# schematic.net
KiCad netlist of a schematic drawn in EAGLE
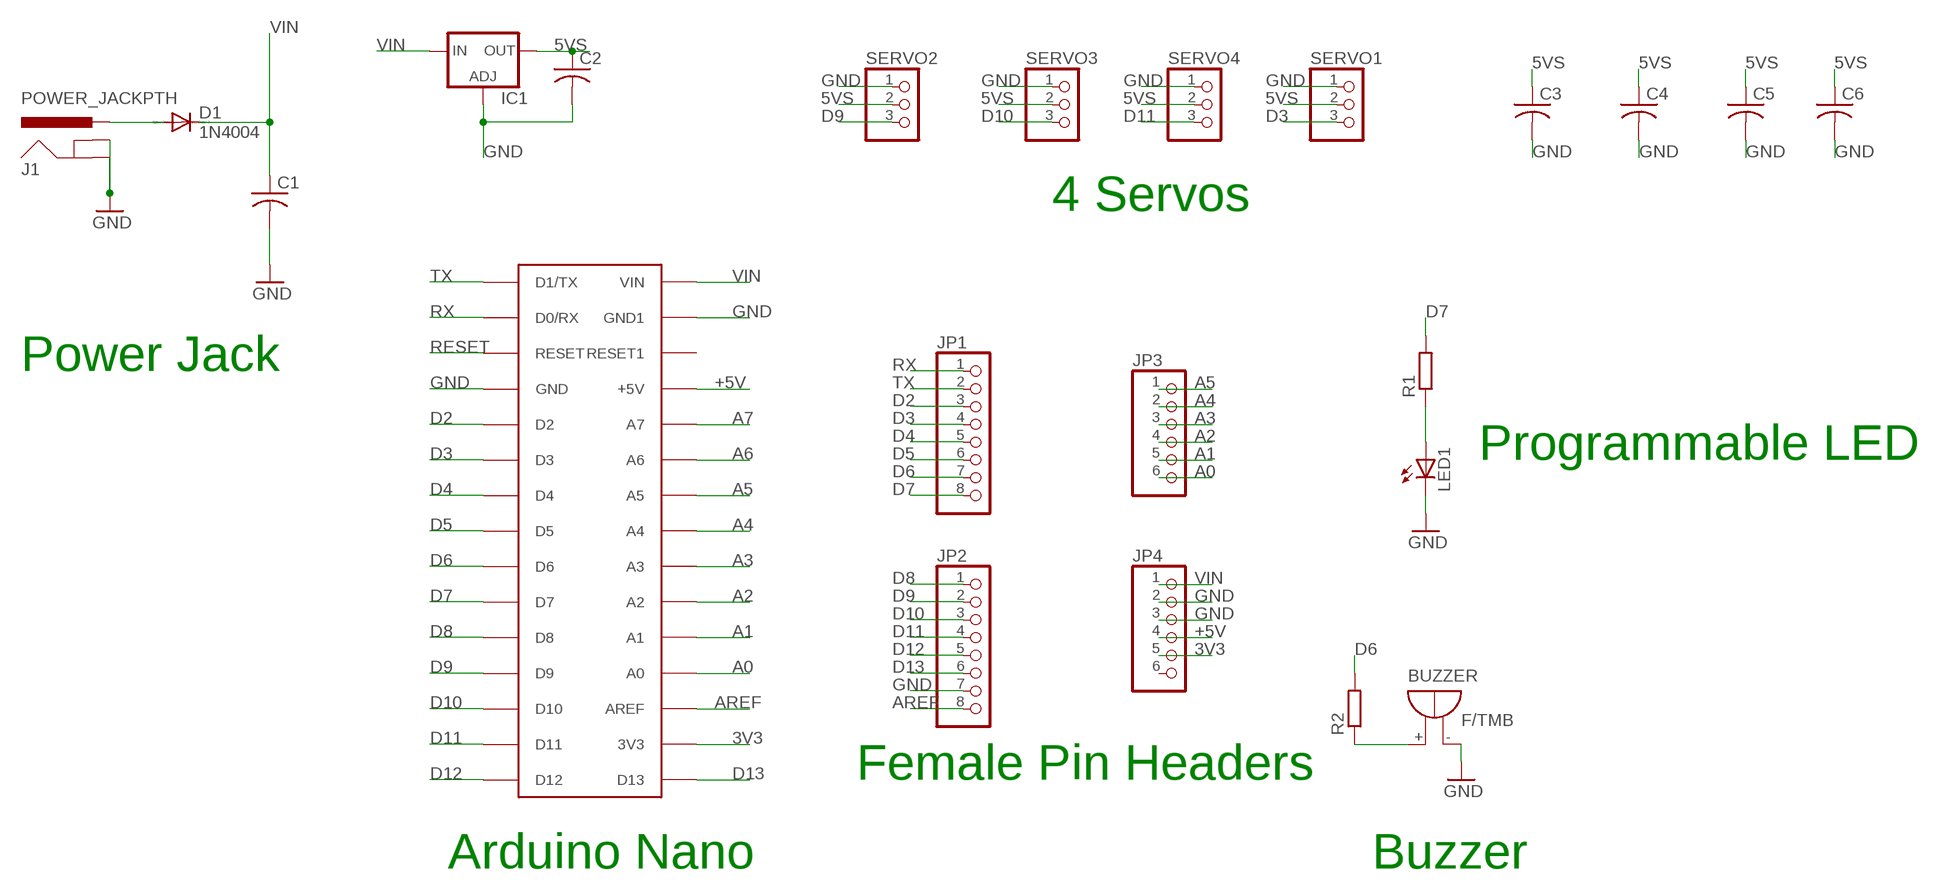
[diagram p0: schematic, sheet 1]

(export (version "E")
  (design (tool "Eeschema 10.0.6"))
  (components
    (comp (ref "BUZZER")
      (value "F/TMB")
      (footprint "eagle-import:F_TMB")
      (libsource (lib "eagle-import") (part "F/TMB"))
    )
    (comp (ref "C1")
      (value "C-USC1206")
      (footprint "eagle-import:C1206")
      (libsource (lib "eagle-import") (part "C-USC1206"))
    )
    (comp (ref "C2")
      (value "C-USC1206")
      (footprint "eagle-import:C1206")
      (libsource (lib "eagle-import") (part "C-USC1206"))
    )
    (comp (ref "C3")
      (value "C-USC0805")
      (footprint "eagle-import:C0805")
      (libsource (lib "eagle-import") (part "C-USC0805"))
    )
    (comp (ref "C4")
      (value "C-USC0805")
      (footprint "eagle-import:C0805")
      (libsource (lib "eagle-import") (part "C-USC0805"))
    )
    (comp (ref "C5")
      (value "C-USC0805")
      (footprint "eagle-import:C0805")
      (libsource (lib "eagle-import") (part "C-USC0805"))
    )
    (comp (ref "C6")
      (value "C-USC0805")
      (footprint "eagle-import:C0805")
      (libsource (lib "eagle-import") (part "C-USC0805"))
    )
    (comp (ref "D1")
      (value "1N4004")
      (footprint "eagle-import:DO41-10")
      (libsource (lib "eagle-import") (part "1N4004"))
    )
    (comp (ref "IC1")
      (value "LD117AS33TR")
      (footprint "eagle-import:SOT223")
      (libsource (lib "eagle-import") (part "LD117A?S33TR"))
    )
    (comp (ref "J1")
      (value "POWER_JACKPTH")
      (footprint "eagle-import:POWER_JACK_PTH")
      (libsource (lib "eagle-import") (part "POWER_JACKPTH"))
    )
    (comp (ref "JP1")
      (value "PINHD-1X8")
      (footprint "eagle-import:1X08")
      (libsource (lib "eagle-import") (part "PINHD-1X8"))
    )
    (comp (ref "JP2")
      (value "PINHD-1X8")
      (footprint "eagle-import:1X08")
      (libsource (lib "eagle-import") (part "PINHD-1X8"))
    )
    (comp (ref "JP3")
      (value "PINHD-1X6")
      (footprint "eagle-import:1X06")
      (libsource (lib "eagle-import") (part "PINHD-1X6"))
    )
    (comp (ref "JP4")
      (value "PINHD-1X6")
      (footprint "eagle-import:1X06")
      (libsource (lib "eagle-import") (part "PINHD-1X6"))
    )
    (comp (ref "LED1")
      (value "LED5MM")
      (footprint "eagle-import:LED5MM")
      (libsource (lib "eagle-import") (part "LED5MM"))
    )
    (comp (ref "R1")
      (value "R-EU_0207/10")
      (footprint "eagle-import:0207_10")
      (libsource (lib "eagle-import") (part "R-EU_0207/10"))
    )
    (comp (ref "R2")
      (value "R-EU_0207/10")
      (footprint "eagle-import:0207_10")
      (libsource (lib "eagle-import") (part "R-EU_0207/10"))
    )
    (comp (ref "SERVO1")
      (value "PINHD-1X3")
      (footprint "eagle-import:1X03")
      (libsource (lib "eagle-import") (part "PINHD-1X3"))
    )
    (comp (ref "SERVO2")
      (value "PINHD-1X3")
      (footprint "eagle-import:1X03")
      (libsource (lib "eagle-import") (part "PINHD-1X3"))
    )
    (comp (ref "SERVO3")
      (value "PINHD-1X3")
      (footprint "eagle-import:1X03")
      (libsource (lib "eagle-import") (part "PINHD-1X3"))
    )
    (comp (ref "SERVO4")
      (value "PINHD-1X3")
      (footprint "eagle-import:1X03")
      (libsource (lib "eagle-import") (part "PINHD-1X3"))
    )
    (comp (ref "U$1")
      (value "ARDUINONANO")
      (footprint "eagle-import:PDIP-32")
      (libsource (lib "eagle-import") (part "ARDUINONANO"))
    )
  )
  (nets
    (net (code "1") (name "/+5V") (class "Default")
      (node (ref "JP4") (pin "4") (pinfunction "4_4") (pintype "passive"))
      (node (ref "U$1") (pin "+5V") (pinfunction "+5V_+5V") (pintype "bidirectional"))
    )
    (net (code "2") (name "/3V3") (class "Default")
      (node (ref "JP4") (pin "5") (pinfunction "5_5") (pintype "passive"))
      (node (ref "U$1") (pin "3V3") (pinfunction "3V3_3V3") (pintype "bidirectional"))
    )
    (net (code "3") (name "/5VS") (class "Default")
      (node (ref "C2") (pin "1") (pinfunction "1_1") (pintype "passive"))
      (node (ref "C3") (pin "1") (pinfunction "1_1") (pintype "passive"))
      (node (ref "C4") (pin "1") (pinfunction "1_1") (pintype "passive"))
      (node (ref "C5") (pin "1") (pinfunction "1_1") (pintype "passive"))
      (node (ref "C6") (pin "1") (pinfunction "1_1") (pintype "passive"))
      (node (ref "IC1") (pin "4") (pinfunction "OUT_4") (pintype "passive"))
      (node (ref "SERVO1") (pin "2") (pinfunction "2_2") (pintype "passive"))
      (node (ref "SERVO2") (pin "2") (pinfunction "2_2") (pintype "passive"))
      (node (ref "SERVO3") (pin "2") (pinfunction "2_2") (pintype "passive"))
      (node (ref "SERVO4") (pin "2") (pinfunction "2_2") (pintype "passive"))
    )
    (net (code "4") (name "/A0") (class "Default")
      (node (ref "JP3") (pin "6") (pinfunction "6_6") (pintype "passive"))
      (node (ref "U$1") (pin "A7") (pinfunction "A0_A7") (pintype "bidirectional"))
    )
    (net (code "5") (name "/A1") (class "Default")
      (node (ref "JP3") (pin "5") (pinfunction "5_5") (pintype "passive"))
      (node (ref "U$1") (pin "A6") (pinfunction "A1_A6") (pintype "bidirectional"))
    )
    (net (code "6") (name "/A2") (class "Default")
      (node (ref "JP3") (pin "4") (pinfunction "4_4") (pintype "passive"))
      (node (ref "U$1") (pin "A5") (pinfunction "A2_A5") (pintype "bidirectional"))
    )
    (net (code "7") (name "/A3") (class "Default")
      (node (ref "JP3") (pin "3") (pinfunction "3_3") (pintype "passive"))
      (node (ref "U$1") (pin "A4") (pinfunction "A3_A4") (pintype "bidirectional"))
    )
    (net (code "8") (name "/A4") (class "Default")
      (node (ref "JP3") (pin "2") (pinfunction "2_2") (pintype "passive"))
      (node (ref "U$1") (pin "A3") (pinfunction "A4_A3") (pintype "bidirectional"))
    )
    (net (code "9") (name "/A5") (class "Default")
      (node (ref "JP3") (pin "1") (pinfunction "1_1") (pintype "passive"))
      (node (ref "U$1") (pin "A2") (pinfunction "A5_A2") (pintype "bidirectional"))
    )
    (net (code "10") (name "/A6") (class "Default")
      (node (ref "U$1") (pin "A1") (pinfunction "A6_A1") (pintype "bidirectional"))
    )
    (net (code "11") (name "/A7") (class "Default")
      (node (ref "U$1") (pin "A0") (pinfunction "A7_A0") (pintype "bidirectional"))
    )
    (net (code "12") (name "/AREF") (class "Default")
      (node (ref "JP2") (pin "8") (pinfunction "8_8") (pintype "passive"))
      (node (ref "U$1") (pin "AREF") (pinfunction "AREF_AREF") (pintype "bidirectional"))
    )
    (net (code "13") (name "/D2") (class "Default")
      (node (ref "JP1") (pin "3") (pinfunction "3_3") (pintype "passive"))
      (node (ref "U$1") (pin "D2") (pinfunction "D2_D2") (pintype "bidirectional"))
    )
    (net (code "14") (name "/D3") (class "Default")
      (node (ref "JP1") (pin "4") (pinfunction "4_4") (pintype "passive"))
      (node (ref "SERVO1") (pin "3") (pinfunction "3_3") (pintype "passive"))
      (node (ref "U$1") (pin "D3") (pinfunction "D3_D3") (pintype "bidirectional"))
    )
    (net (code "15") (name "/D4") (class "Default")
      (node (ref "JP1") (pin "5") (pinfunction "5_5") (pintype "passive"))
      (node (ref "U$1") (pin "D4") (pinfunction "D4_D4") (pintype "bidirectional"))
    )
    (net (code "16") (name "/D5") (class "Default")
      (node (ref "JP1") (pin "6") (pinfunction "6_6") (pintype "passive"))
      (node (ref "U$1") (pin "D5") (pinfunction "D5_D5") (pintype "bidirectional"))
    )
    (net (code "17") (name "/D6") (class "Default")
      (node (ref "JP1") (pin "7") (pinfunction "7_7") (pintype "passive"))
      (node (ref "R2") (pin "2") (pinfunction "2_2") (pintype "passive"))
      (node (ref "U$1") (pin "D6") (pinfunction "D6_D6") (pintype "bidirectional"))
    )
    (net (code "18") (name "/D7") (class "Default")
      (node (ref "JP1") (pin "8") (pinfunction "8_8") (pintype "passive"))
      (node (ref "R1") (pin "2") (pinfunction "2_2") (pintype "passive"))
      (node (ref "U$1") (pin "D7") (pinfunction "D7_D7") (pintype "bidirectional"))
    )
    (net (code "19") (name "/D8") (class "Default")
      (node (ref "JP2") (pin "1") (pinfunction "1_1") (pintype "passive"))
      (node (ref "U$1") (pin "D8") (pinfunction "D8_D8") (pintype "bidirectional"))
    )
    (net (code "20") (name "/D9") (class "Default")
      (node (ref "JP2") (pin "2") (pinfunction "2_2") (pintype "passive"))
      (node (ref "SERVO2") (pin "3") (pinfunction "3_3") (pintype "passive"))
      (node (ref "U$1") (pin "D9") (pinfunction "D9_D9") (pintype "bidirectional"))
    )
    (net (code "21") (name "/D10") (class "Default")
      (node (ref "JP2") (pin "3") (pinfunction "3_3") (pintype "passive"))
      (node (ref "SERVO3") (pin "3") (pinfunction "3_3") (pintype "passive"))
      (node (ref "U$1") (pin "D10") (pinfunction "D10_D10") (pintype "bidirectional"))
    )
    (net (code "22") (name "/D11") (class "Default")
      (node (ref "JP2") (pin "4") (pinfunction "4_4") (pintype "passive"))
      (node (ref "SERVO4") (pin "3") (pinfunction "3_3") (pintype "passive"))
      (node (ref "U$1") (pin "D11") (pinfunction "D11_D11") (pintype "bidirectional"))
    )
    (net (code "23") (name "/D12") (class "Default")
      (node (ref "JP2") (pin "5") (pinfunction "5_5") (pintype "passive"))
      (node (ref "U$1") (pin "D12") (pinfunction "D12_D12") (pintype "bidirectional"))
    )
    (net (code "24") (name "/D13") (class "Default")
      (node (ref "JP2") (pin "6") (pinfunction "6_6") (pintype "passive"))
      (node (ref "U$1") (pin "D13") (pinfunction "D13_D13") (pintype "bidirectional"))
    )
    (net (code "25") (name "/RESET") (class "Default")
      (node (ref "U$1") (pin "RESET") (pinfunction "RESET_RESET") (pintype "bidirectional"))
    )
    (net (code "26") (name "/RX") (class "Default")
      (node (ref "JP1") (pin "1") (pinfunction "1_1") (pintype "passive"))
      (node (ref "U$1") (pin "D0/RX") (pinfunction "D0/RX_D0/RX") (pintype "bidirectional"))
    )
    (net (code "27") (name "/TX") (class "Default")
      (node (ref "JP1") (pin "2") (pinfunction "2_2") (pintype "passive"))
      (node (ref "U$1") (pin "D1/TX") (pinfunction "D1/TX_D1/TX") (pintype "bidirectional"))
    )
    (net (code "28") (name "/VIN") (class "Default")
      (node (ref "C1") (pin "1") (pinfunction "1_1") (pintype "passive"))
      (node (ref "D1") (pin "C") (pinfunction "C_C") (pintype "passive"))
      (node (ref "IC1") (pin "3") (pinfunction "IN_3") (pintype "input"))
      (node (ref "JP4") (pin "1") (pinfunction "1_1") (pintype "passive"))
      (node (ref "U$1") (pin "VIN") (pinfunction "VIN_VIN") (pintype "bidirectional"))
    )
    (net (code "29") (name "GND") (class "Default")
      (node (ref "BUZZER") (pin "-") (pinfunction "-_-") (pintype "passive"))
      (node (ref "C1") (pin "2") (pinfunction "2_2") (pintype "passive"))
      (node (ref "C2") (pin "2") (pinfunction "2_2") (pintype "passive"))
      (node (ref "C3") (pin "2") (pinfunction "2_2") (pintype "passive"))
      (node (ref "C4") (pin "2") (pinfunction "2_2") (pintype "passive"))
      (node (ref "C5") (pin "2") (pinfunction "2_2") (pintype "passive"))
      (node (ref "C6") (pin "2") (pinfunction "2_2") (pintype "passive"))
      (node (ref "IC1") (pin "1") (pinfunction "ADJ_1") (pintype "input"))
      (node (ref "J1") (pin "GND") (pinfunction "GND_GND") (pintype "bidirectional"))
      (node (ref "J1") (pin "GNDBREAK") (pinfunction "GNDBREAK_GNDBREAK") (pintype "bidirectional"))
      (node (ref "JP2") (pin "7") (pinfunction "7_7") (pintype "passive"))
      (node (ref "JP4") (pin "2") (pinfunction "2_2") (pintype "passive"))
      (node (ref "JP4") (pin "3") (pinfunction "3_3") (pintype "passive"))
      (node (ref "LED1") (pin "K") (pinfunction "C_K") (pintype "passive"))
      (node (ref "SERVO1") (pin "1") (pinfunction "1_1") (pintype "passive"))
      (node (ref "SERVO2") (pin "1") (pinfunction "1_1") (pintype "passive"))
      (node (ref "SERVO3") (pin "1") (pinfunction "1_1") (pintype "passive"))
      (node (ref "SERVO4") (pin "1") (pinfunction "1_1") (pintype "passive"))
      (node (ref "U$1") (pin "GND") (pinfunction "GND_GND") (pintype "bidirectional"))
      (node (ref "U$1") (pin "GND1") (pinfunction "GND1_GND1") (pintype "bidirectional"))
    )
    (net (code "30") (name "Net-(BUZZER-Pad+)") (class "Default")
      (node (ref "BUZZER") (pin "+") (pinfunction "+_+") (pintype "passive"))
      (node (ref "R2") (pin "1") (pinfunction "1_1") (pintype "passive"))
    )
    (net (code "31") (name "Net-(D1-PadA)") (class "Default")
      (node (ref "D1") (pin "A") (pinfunction "A_A") (pintype "passive"))
      (node (ref "J1") (pin "PWR") (pinfunction "PWR_PWR") (pintype "bidirectional"))
    )
    (net (code "32") (name "Net-(LED1-PadA)") (class "Default")
      (node (ref "LED1") (pin "A") (pinfunction "A_A") (pintype "passive"))
      (node (ref "R1") (pin "1") (pinfunction "1_1") (pintype "passive"))
    )
    (net (code "33") (name "unconnected-(JP4-Pad6)") (class "Default")
      (node (ref "JP4") (pin "6") (pinfunction "6_6") (pintype "passive"))
    )
    (net (code "34") (name "unconnected-(U$1-PadRESET1)") (class "Default")
      (node (ref "U$1") (pin "RESET1") (pinfunction "RESET1_RESET1") (pintype "bidirectional"))
    )
  )
)
